# Adafruit_Feather_M0_WiFi.net
KiCad netlist of a schematic drawn in EAGLE
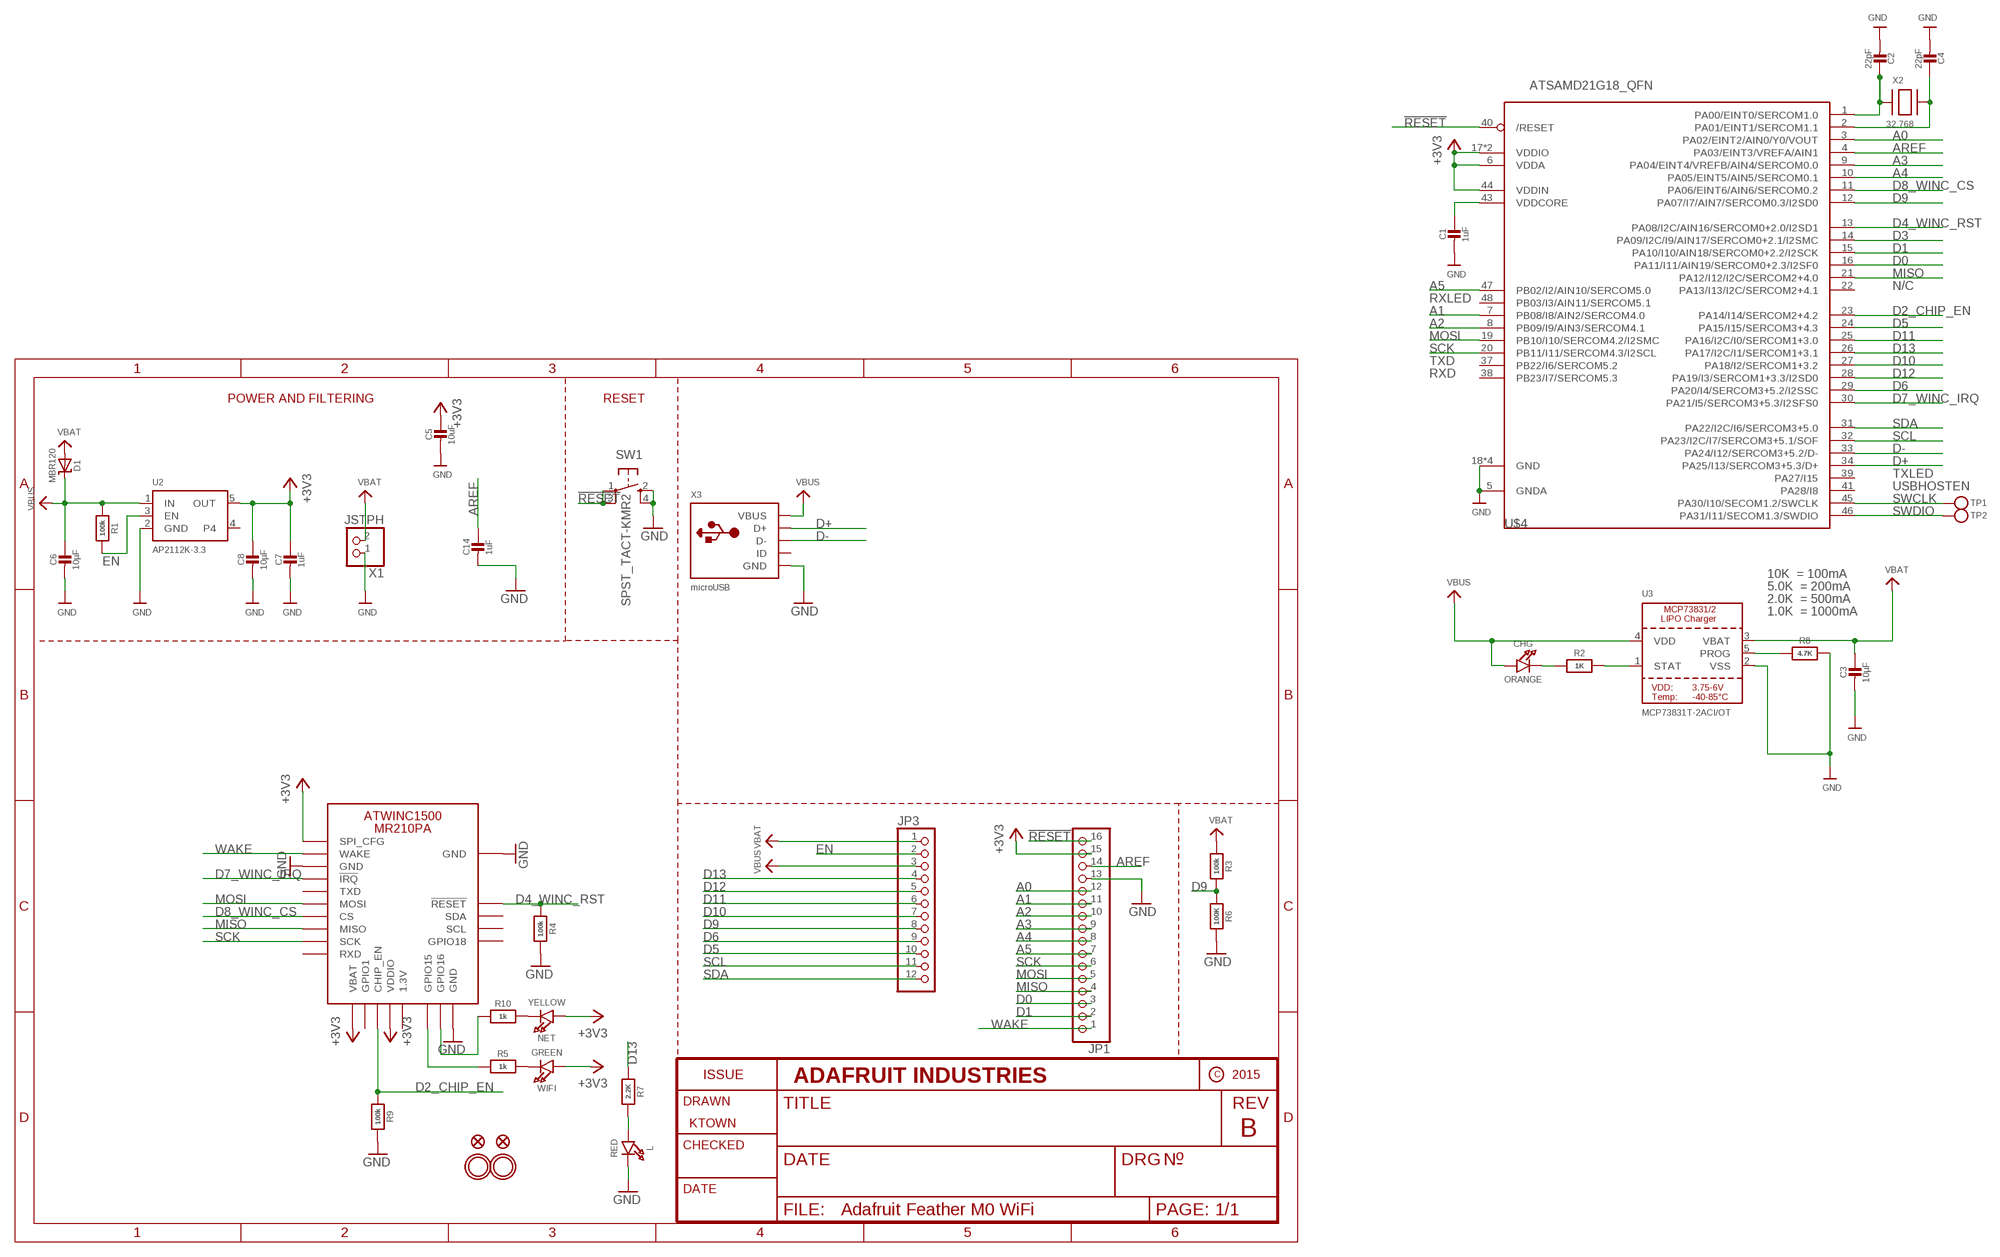
[diagram p0: schematic, sheet 1]

(export (version "E")
  (design (tool "Eeschema 10.0.6"))
  (components
    (comp (ref "C1")
      (value "1uF")
      (footprint "eagle-import:0603-NO")
      (libsource (lib "eagle-import") (part "CAP_CERAMIC0603_NO"))
    )
    (comp (ref "C2")
      (value "22pF")
      (footprint "eagle-import:0603-NO")
      (libsource (lib "eagle-import") (part "CAP_CERAMIC0603_NO"))
    )
    (comp (ref "C3")
      (value "10µF")
      (footprint "eagle-import:0805-NO")
      (libsource (lib "eagle-import") (part "CAP_CERAMIC0805-NOOUTLINE"))
    )
    (comp (ref "C4")
      (value "22pF")
      (footprint "eagle-import:0603-NO")
      (libsource (lib "eagle-import") (part "CAP_CERAMIC0603_NO"))
    )
    (comp (ref "C5")
      (value "10uF")
      (footprint "eagle-import:0805-NO")
      (libsource (lib "eagle-import") (part "CAP_CERAMIC0805-NOOUTLINE"))
    )
    (comp (ref "C6")
      (value "10µF")
      (footprint "eagle-import:0805-NO")
      (libsource (lib "eagle-import") (part "CAP_CERAMIC0805-NOOUTLINE"))
    )
    (comp (ref "C7")
      (value "1uF")
      (footprint "eagle-import:0603-NO")
      (libsource (lib "eagle-import") (part "CAP_CERAMIC0603_NO"))
    )
    (comp (ref "C8")
      (value "10µF")
      (footprint "eagle-import:0805-NO")
      (libsource (lib "eagle-import") (part "CAP_CERAMIC0805-NOOUTLINE"))
    )
    (comp (ref "C14")
      (value "1uF")
      (footprint "eagle-import:0603-NO")
      (libsource (lib "eagle-import") (part "CAP_CERAMIC0603_NO"))
    )
    (comp (ref "CHG")
      (value "ORANGE")
      (footprint "eagle-import:CHIPLED_0805_NOOUTLINE")
      (libsource (lib "eagle-import") (part "LED0805_NOOUTLINE"))
    )
    (comp (ref "D1")
      (value "MBR120")
      (footprint "eagle-import:SOD-123")
      (libsource (lib "eagle-import") (part "DIODE-SCHOTTKYSOD-123"))
    )
    (comp (ref "JP1")
      (value "HEADER-1X16ROUND")
      (footprint "eagle-import:1X16_ROUND")
      (libsource (lib "eagle-import") (part "HEADER-1X16ROUND"))
    )
    (comp (ref "JP3")
      (value "HEADER-1X12")
      (footprint "eagle-import:1X12_ROUND")
      (libsource (lib "eagle-import") (part "HEADER-1X12"))
    )
    (comp (ref "L")
      (value "RED")
      (footprint "eagle-import:CHIPLED_0805_NOOUTLINE")
      (libsource (lib "eagle-import") (part "LED0805_NOOUTLINE"))
    )
    (comp (ref "NET")
      (value "YELLOW")
      (footprint "eagle-import:CHIPLED_0805_NOOUTLINE")
      (libsource (lib "eagle-import") (part "LED0805_NOOUTLINE"))
    )
    (comp (ref "R1")
      (value "100k")
      (footprint "eagle-import:0603-NO")
      (libsource (lib "eagle-import") (part "RESISTOR_0603_NOOUT"))
    )
    (comp (ref "R2")
      (value "1K")
      (footprint "eagle-import:0603-NO")
      (libsource (lib "eagle-import") (part "RESISTOR_0603_NOOUT"))
    )
    (comp (ref "R3")
      (value "100k")
      (footprint "eagle-import:0603-NO")
      (libsource (lib "eagle-import") (part "RESISTOR_0603_NOOUT"))
    )
    (comp (ref "R4")
      (value "100k")
      (footprint "eagle-import:0603-NO")
      (libsource (lib "eagle-import") (part "RESISTOR_0603_NOOUT"))
    )
    (comp (ref "R5")
      (value "1k")
      (footprint "eagle-import:0603-NO")
      (libsource (lib "eagle-import") (part "RESISTOR_0603_NOOUT"))
    )
    (comp (ref "R6")
      (value "100K")
      (footprint "eagle-import:0603-NO")
      (libsource (lib "eagle-import") (part "RESISTOR_0603_NOOUT"))
    )
    (comp (ref "R7")
      (value "2.2K")
      (footprint "eagle-import:0603-NO")
      (libsource (lib "eagle-import") (part "RESISTOR_0603_NOOUT"))
    )
    (comp (ref "R8")
      (value "4.7K")
      (footprint "eagle-import:0603-NO")
      (libsource (lib "eagle-import") (part "RESISTOR_0603_NOOUT"))
    )
    (comp (ref "R9")
      (value "100k")
      (footprint "eagle-import:0603-NO")
      (libsource (lib "eagle-import") (part "RESISTOR_0603_NOOUT"))
    )
    (comp (ref "R10")
      (value "1k")
      (footprint "eagle-import:0603-NO")
      (libsource (lib "eagle-import") (part "RESISTOR_0603_NOOUT"))
    )
    (comp (ref "SW1")
      (value "SPST_TACT-KMR2")
      (footprint "eagle-import:KMR2")
      (libsource (lib "eagle-import") (part "SPST_TACT-KMR2"))
    )
    (comp (ref "TP1")
      (value "TESTPOINTROUND1.5MM")
      (footprint "eagle-import:TESTPOINT_ROUND_1.5MM")
      (libsource (lib "eagle-import") (part "TESTPOINTROUND1.5MM"))
    )
    (comp (ref "TP2")
      (value "TESTPOINTROUND1.5MM")
      (footprint "eagle-import:TESTPOINT_ROUND_1.5MM")
      (libsource (lib "eagle-import") (part "TESTPOINTROUND1.5MM"))
    )
    (comp (ref "U$4")
      (value "ATSAMD21G18_QFN")
      (footprint "eagle-import:TQFN48_7MM")
      (libsource (lib "eagle-import") (part "ATSAMD21J_QFN"))
    )
    (comp (ref "U$31")
      (value "MOUNTINGHOLE2.5")
      (footprint "eagle-import:MOUNTINGHOLE_2.5_PLATED")
      (libsource (lib "eagle-import") (part "MOUNTINGHOLE2.5"))
    )
    (comp (ref "U$32")
      (value "MOUNTINGHOLE2.5")
      (footprint "eagle-import:MOUNTINGHOLE_2.5_PLATED")
      (libsource (lib "eagle-import") (part "MOUNTINGHOLE2.5"))
    )
    (comp (ref "U$34")
      (value "FIDUCIAL\"\"")
      (footprint "eagle-import:FIDUCIAL_1MM")
      (libsource (lib "eagle-import") (part "FIDUCIAL{dblquote}{dblquote}"))
    )
    (comp (ref "U$35")
      (value "FIDUCIAL\"\"")
      (footprint "eagle-import:FIDUCIAL_1MM")
      (libsource (lib "eagle-import") (part "FIDUCIAL{dblquote}{dblquote}"))
    )
    (comp (ref "U2")
      (value "AP2112K-3.3")
      (footprint "eagle-import:SOT23-5")
      (libsource (lib "eagle-import") (part "VREG_SOT23-5"))
    )
    (comp (ref "U3")
      (value "MCP73831T-2ACI/OT")
      (footprint "eagle-import:SOT23-5")
      (libsource (lib "eagle-import") (part "MCP73831/2"))
    )
    (comp (ref "WIFI")
      (value "GREEN")
      (footprint "eagle-import:CHIPLED_0805_NOOUTLINE")
      (libsource (lib "eagle-import") (part "LED0805_NOOUTLINE"))
    )
    (comp (ref "X1")
      (value "JSTPH")
      (footprint "eagle-import:JSTPH2")
      (libsource (lib "eagle-import") (part "CON_JST_PH_2PIN"))
    )
    (comp (ref "X2")
      (value "32.768")
      (footprint "eagle-import:XTAL3215")
      (libsource (lib "eagle-import") (part "XTAL-3.2X1.5"))
    )
    (comp (ref "X3")
      (value "microUSB")
      (footprint "eagle-import:4UCONN_20329_V2")
      (libsource (lib "eagle-import") (part "USB_MICRO_20329_V2"))
    )
    (comp (ref "X4")
      (value "ATWINC1500_MR210PA")
      (footprint "eagle-import:ATWINC1500_MR210PA")
      (libsource (lib "eagle-import") (part "ATWINC1500_MR210PA"))
    )
  )
  (nets
    (net (code "1") (name "+3V3") (class "Default")
      (node (ref "C5") (pin "1") (pinfunction "1_1") (pintype "passive"))
      (node (ref "C7") (pin "1") (pinfunction "1_1") (pintype "passive"))
      (node (ref "C8") (pin "1") (pinfunction "1_1") (pintype "passive"))
      (node (ref "JP1") (pin "15") (pinfunction "15_15") (pintype "passive"))
      (node (ref "NET") (pin "A") (pinfunction "A_A") (pintype "passive"))
      (node (ref "U$4") (pin "17") (pinfunction "VDDIO_17") (pintype "power_in"))
      (node (ref "U$4") (pin "36") (pinfunction "VDDIO_36") (pintype "power_in"))
      (node (ref "U$4") (pin "44") (pinfunction "VDDIN_44") (pintype "power_in"))
      (node (ref "U$4") (pin "6") (pinfunction "VDDA_6") (pintype "power_in"))
      (node (ref "U2") (pin "5") (pinfunction "OUT_5") (pintype "power_in"))
      (node (ref "WIFI") (pin "A") (pinfunction "A_A") (pintype "passive"))
      (node (ref "X4") (pin "J10") (pinfunction "SPI_CFG_J10") (pintype "input"))
      (node (ref "X4") (pin "J20") (pinfunction "VBAT_J20") (pintype "power_in"))
      (node (ref "X4") (pin "J23") (pinfunction "VDDIO_J23") (pintype "power_in"))
    )
    (net (code "2") (name "/A0") (class "Default")
      (node (ref "JP1") (pin "12") (pinfunction "12_12") (pintype "passive"))
      (node (ref "U$4") (pin "3") (pinfunction "PA02/EINT2/AIN0/Y0/VOUT_3") (pintype "bidirectional"))
    )
    (net (code "3") (name "/A1") (class "Default")
      (node (ref "JP1") (pin "11") (pinfunction "11_11") (pintype "passive"))
      (node (ref "U$4") (pin "7") (pinfunction "PB08/I8/AIN2/SERCOM4.0_7") (pintype "bidirectional"))
    )
    (net (code "4") (name "/A2") (class "Default")
      (node (ref "JP1") (pin "10") (pinfunction "10_10") (pintype "passive"))
      (node (ref "U$4") (pin "8") (pinfunction "PB09/I9/AIN3/SERCOM4.1_8") (pintype "bidirectional"))
    )
    (net (code "5") (name "/A3") (class "Default")
      (node (ref "JP1") (pin "9") (pinfunction "9_9") (pintype "passive"))
      (node (ref "U$4") (pin "9") (pinfunction "PA04/EINT4/VREFB/AIN4/SERCOM0.0_9") (pintype "bidirectional"))
    )
    (net (code "6") (name "/A4") (class "Default")
      (node (ref "JP1") (pin "8") (pinfunction "8_8") (pintype "passive"))
      (node (ref "U$4") (pin "10") (pinfunction "PA05/EINT5/AIN5/SERCOM0.1_10") (pintype "bidirectional"))
    )
    (net (code "7") (name "/A5") (class "Default")
      (node (ref "JP1") (pin "7") (pinfunction "7_7") (pintype "passive"))
      (node (ref "U$4") (pin "47") (pinfunction "PB02/I2/AIN10/SERCOM5.0_47") (pintype "bidirectional"))
    )
    (net (code "8") (name "/AREF") (class "Default")
      (node (ref "C14") (pin "1") (pinfunction "1_1") (pintype "passive"))
      (node (ref "JP1") (pin "14") (pinfunction "14_14") (pintype "passive"))
      (node (ref "U$4") (pin "4") (pinfunction "PA03/EINT3/VREFA/AIN1_4") (pintype "bidirectional"))
    )
    (net (code "9") (name "/D+") (class "Default")
      (node (ref "U$4") (pin "34") (pinfunction "PA25/I13/SERCOM3+5.3/D+_34") (pintype "bidirectional"))
      (node (ref "X3") (pin "D+") (pinfunction "D+_D+") (pintype "bidirectional"))
    )
    (net (code "10") (name "/D-") (class "Default")
      (node (ref "U$4") (pin "33") (pinfunction "PA24/I12/SERCOM3+5.2/D-_33") (pintype "bidirectional"))
      (node (ref "X3") (pin "D-") (pinfunction "D-_D-") (pintype "bidirectional"))
    )
    (net (code "11") (name "/D0") (class "Default")
      (node (ref "JP1") (pin "3") (pinfunction "3_3") (pintype "passive"))
      (node (ref "U$4") (pin "16") (pinfunction "PA11/I11/AIN19/SERCOM0+2.3/I2SF0_16") (pintype "bidirectional"))
    )
    (net (code "12") (name "/D1") (class "Default")
      (node (ref "JP1") (pin "2") (pinfunction "2_2") (pintype "passive"))
      (node (ref "U$4") (pin "15") (pinfunction "PA10/I10/AIN18/SERCOM0+2.2/I2SCK_15") (pintype "bidirectional"))
    )
    (net (code "13") (name "/D2_CHIP_EN") (class "Default")
      (node (ref "R9") (pin "1") (pinfunction "1_1") (pintype "passive"))
      (node (ref "U$4") (pin "23") (pinfunction "PA14/I14/SERCOM2+4.2_23") (pintype "bidirectional"))
      (node (ref "X4") (pin "J22") (pinfunction "CHIP_EN_J22") (pintype "input"))
    )
    (net (code "14") (name "/D3") (class "Default")
      (node (ref "U$4") (pin "14") (pinfunction "PA09/I2C/I9/AIN17/SERCOM0+2.1/I2SMC_14") (pintype "bidirectional"))
    )
    (net (code "15") (name "/D4_WINC_RST") (class "Default")
      (node (ref "R4") (pin "1") (pinfunction "1_1") (pintype "passive"))
      (node (ref "U$4") (pin "13") (pinfunction "PA08/I2C/AIN16/SERCOM0+2.0/I2SD1_13") (pintype "bidirectional"))
      (node (ref "X4") (pin "J4") (pinfunction "~{RESET}_J4") (pintype "input"))
    )
    (net (code "16") (name "/D5") (class "Default")
      (node (ref "JP3") (pin "10") (pinfunction "10_10") (pintype "passive"))
      (node (ref "U$4") (pin "24") (pinfunction "PA15/I15/SERCOM3+4.3_24") (pintype "bidirectional"))
    )
    (net (code "17") (name "/D6") (class "Default")
      (node (ref "JP3") (pin "9") (pinfunction "9_9") (pintype "passive"))
      (node (ref "U$4") (pin "29") (pinfunction "PA20/I4/SERCOM3+5.2/I2SSC_29") (pintype "bidirectional"))
    )
    (net (code "18") (name "/D7_WINC_IRQ") (class "Default")
      (node (ref "U$4") (pin "30") (pinfunction "PA21/I5/SERCOM3+5.3/I2SFS0_30") (pintype "bidirectional"))
      (node (ref "X4") (pin "J13") (pinfunction "~{IRQ}_J13") (pintype "output"))
    )
    (net (code "19") (name "/D8_WINC_CS") (class "Default")
      (node (ref "U$4") (pin "11") (pinfunction "PA06/EINT6/AIN6/SERCOM0.2_11") (pintype "bidirectional"))
      (node (ref "X4") (pin "J16") (pinfunction "CS_J16") (pintype "input"))
    )
    (net (code "20") (name "/D9") (class "Default")
      (node (ref "JP3") (pin "8") (pinfunction "8_8") (pintype "passive"))
      (node (ref "R3") (pin "2") (pinfunction "2_2") (pintype "passive"))
      (node (ref "R6") (pin "1") (pinfunction "1_1") (pintype "passive"))
      (node (ref "U$4") (pin "12") (pinfunction "PA07/I7/AIN7/SERCOM0.3/I2SD0_12") (pintype "bidirectional"))
    )
    (net (code "21") (name "/D10") (class "Default")
      (node (ref "JP3") (pin "7") (pinfunction "7_7") (pintype "passive"))
      (node (ref "U$4") (pin "27") (pinfunction "PA18/I2/SERCOM1+3.2_27") (pintype "bidirectional"))
    )
    (net (code "22") (name "/D11") (class "Default")
      (node (ref "JP3") (pin "6") (pinfunction "6_6") (pintype "passive"))
      (node (ref "U$4") (pin "25") (pinfunction "PA16/I2C/I0/SERCOM1+3.0_25") (pintype "bidirectional"))
    )
    (net (code "23") (name "/D12") (class "Default")
      (node (ref "JP3") (pin "5") (pinfunction "5_5") (pintype "passive"))
      (node (ref "U$4") (pin "28") (pinfunction "PA19/I3/SERCOM1+3.3/I2SD0_28") (pintype "bidirectional"))
    )
    (net (code "24") (name "/D13") (class "Default")
      (node (ref "JP3") (pin "4") (pinfunction "4_4") (pintype "passive"))
      (node (ref "R7") (pin "1") (pinfunction "1_1") (pintype "passive"))
      (node (ref "U$4") (pin "26") (pinfunction "PA17/I2C/I1/SERCOM1+3.1_26") (pintype "bidirectional"))
    )
    (net (code "25") (name "/EN") (class "Default")
      (node (ref "JP3") (pin "2") (pinfunction "2_2") (pintype "passive"))
      (node (ref "R1") (pin "2") (pinfunction "2_2") (pintype "passive"))
      (node (ref "U2") (pin "3") (pinfunction "EN_3") (pintype "input"))
    )
    (net (code "26") (name "/MISO") (class "Default")
      (node (ref "JP1") (pin "4") (pinfunction "4_4") (pintype "passive"))
      (node (ref "U$4") (pin "21") (pinfunction "PA12/I12/I2C/SERCOM2+4.0_21") (pintype "bidirectional"))
      (node (ref "X4") (pin "J17") (pinfunction "MISO_J17") (pintype "output"))
    )
    (net (code "27") (name "/MOSI") (class "Default")
      (node (ref "JP1") (pin "5") (pinfunction "5_5") (pintype "passive"))
      (node (ref "U$4") (pin "19") (pinfunction "PB10/I10/SERCOM4.2/I2SMC_19") (pintype "bidirectional"))
      (node (ref "X4") (pin "J15") (pinfunction "MOSI_J15") (pintype "input"))
    )
    (net (code "28") (name "/SCK") (class "Default")
      (node (ref "JP1") (pin "6") (pinfunction "6_6") (pintype "passive"))
      (node (ref "U$4") (pin "20") (pinfunction "PB11/I11/SERCOM4.3/I2SCL_20") (pintype "bidirectional"))
      (node (ref "X4") (pin "J18") (pinfunction "SCK_J18") (pintype "input"))
    )
    (net (code "29") (name "/SCL") (class "Default")
      (node (ref "JP3") (pin "11") (pinfunction "11_11") (pintype "passive"))
      (node (ref "U$4") (pin "32") (pinfunction "PA23/I2C/I7/SERCOM3+5.1/SOF_32") (pintype "bidirectional"))
    )
    (net (code "30") (name "/SDA") (class "Default")
      (node (ref "JP3") (pin "12") (pinfunction "12_12") (pintype "passive"))
      (node (ref "U$4") (pin "31") (pinfunction "PA22/I2C/I6/SERCOM3+5.0_31") (pintype "bidirectional"))
    )
    (net (code "31") (name "/SWCLK") (class "Default")
      (node (ref "TP1") (pin "P$1") (pinfunction "P$1_P$1") (pintype "bidirectional"))
      (node (ref "U$4") (pin "45") (pinfunction "PA30/I10/SECOM1.2/SWCLK_45") (pintype "bidirectional"))
    )
    (net (code "32") (name "/SWDIO") (class "Default")
      (node (ref "TP2") (pin "P$1") (pinfunction "P$1_P$1") (pintype "bidirectional"))
      (node (ref "U$4") (pin "46") (pinfunction "PA31/I11/SECOM1.3/SWDIO_46") (pintype "bidirectional"))
    )
    (net (code "33") (name "/WAKE") (class "Default")
      (node (ref "JP1") (pin "1") (pinfunction "1_1") (pintype "passive"))
      (node (ref "X4") (pin "J11") (pinfunction "WAKE_J11") (pintype "input"))
    )
    (net (code "34") (name "/~{RESET}") (class "Default")
      (node (ref "JP1") (pin "16") (pinfunction "16_16") (pintype "passive"))
      (node (ref "SW1") (pin "1") (pinfunction "P_1") (pintype "passive"))
      (node (ref "SW1") (pin "3") (pinfunction "P1_3") (pintype "passive"))
      (node (ref "U$4") (pin "40") (pinfunction "/RESET_40") (pintype "bidirectional"))
    )
    (net (code "35") (name "GND") (class "Default")
      (node (ref "C1") (pin "2") (pinfunction "2_2") (pintype "passive"))
      (node (ref "C14") (pin "2") (pinfunction "2_2") (pintype "passive"))
      (node (ref "C2") (pin "2") (pinfunction "2_2") (pintype "passive"))
      (node (ref "C3") (pin "2") (pinfunction "2_2") (pintype "passive"))
      (node (ref "C4") (pin "2") (pinfunction "2_2") (pintype "passive"))
      (node (ref "C5") (pin "2") (pinfunction "2_2") (pintype "passive"))
      (node (ref "C6") (pin "2") (pinfunction "2_2") (pintype "passive"))
      (node (ref "C7") (pin "2") (pinfunction "2_2") (pintype "passive"))
      (node (ref "C8") (pin "2") (pinfunction "2_2") (pintype "passive"))
      (node (ref "JP1") (pin "13") (pinfunction "13_13") (pintype "passive"))
      (node (ref "L") (pin "C") (pinfunction "C_C") (pintype "passive"))
      (node (ref "R4") (pin "2") (pinfunction "2_2") (pintype "passive"))
      (node (ref "R6") (pin "2") (pinfunction "2_2") (pintype "passive"))
      (node (ref "R8") (pin "2") (pinfunction "2_2") (pintype "passive"))
      (node (ref "R9") (pin "2") (pinfunction "2_2") (pintype "passive"))
      (node (ref "SW1") (pin "2") (pinfunction "S_2") (pintype "passive"))
      (node (ref "SW1") (pin "4") (pinfunction "S1_4") (pintype "passive"))
      (node (ref "U$4") (pin "18") (pinfunction "GND_18") (pintype "power_in"))
      (node (ref "U$4") (pin "35") (pinfunction "GND_35") (pintype "power_in"))
      (node (ref "U$4") (pin "42") (pinfunction "GND_42") (pintype "power_in"))
      (node (ref "U$4") (pin "5") (pinfunction "GNDA_5") (pintype "power_in"))
      (node (ref "U$4") (pin "THERMAL") (pinfunction "GND_THERMAL") (pintype "power_in"))
      (node (ref "U2") (pin "2") (pinfunction "GND_2") (pintype "power_in"))
      (node (ref "U3") (pin "2") (pinfunction "VSS_2") (pintype "power_in"))
      (node (ref "X1") (pin "1") (pinfunction "1_1") (pintype "passive"))
      (node (ref "X3") (pin "BASE@1") (pinfunction "GND_BASE@1") (pintype "power_in"))
      (node (ref "X3") (pin "BASE@2") (pinfunction "GND_BASE@2") (pintype "power_in"))
      (node (ref "X3") (pin "GND") (pinfunction "GND_GND") (pintype "power_in"))
      (node (ref "X3") (pin "SPRT@1") (pinfunction "GND_SPRT@1") (pintype "power_in"))
      (node (ref "X3") (pin "SPRT@2") (pinfunction "GND_SPRT@2") (pintype "power_in"))
      (node (ref "X3") (pin "SPRT@3") (pinfunction "GND_SPRT@3") (pintype "power_in"))
      (node (ref "X3") (pin "SPRT@4") (pinfunction "GND_SPRT@4") (pintype "power_in"))
      (node (ref "X4") (pin "J12") (pinfunction "GND_J12") (pintype "power_in"))
      (node (ref "X4") (pin "J28") (pinfunction "GND_J28") (pintype "power_in"))
      (node (ref "X4") (pin "J9") (pinfunction "GND_J9") (pintype "bidirectional"))
    )
    (net (code "36") (name "Net-(CHG-PadC)") (class "Default")
      (node (ref "CHG") (pin "C") (pinfunction "C_C") (pintype "passive"))
      (node (ref "R2") (pin "1") (pinfunction "1_1") (pintype "passive"))
    )
    (net (code "37") (name "Net-(L-PadA)") (class "Default")
      (node (ref "L") (pin "A") (pinfunction "A_A") (pintype "passive"))
      (node (ref "R7") (pin "2") (pinfunction "2_2") (pintype "passive"))
    )
    (net (code "38") (name "Net-(NET-PadC)") (class "Default")
      (node (ref "NET") (pin "C") (pinfunction "C_C") (pintype "passive"))
      (node (ref "R10") (pin "2") (pinfunction "2_2") (pintype "passive"))
    )
    (net (code "39") (name "Net-(R5-Pad2)") (class "Default")
      (node (ref "R5") (pin "2") (pinfunction "2_2") (pintype "passive"))
      (node (ref "WIFI") (pin "C") (pinfunction "C_C") (pintype "passive"))
    )
    (net (code "40") (name "Net-(U$4-PA00{slash}EINT0{slash}SERCOM1.0)") (class "Default")
      (node (ref "C2") (pin "1") (pinfunction "1_1") (pintype "passive"))
      (node (ref "U$4") (pin "1") (pinfunction "PA00/EINT0/SERCOM1.0_1") (pintype "bidirectional"))
      (node (ref "X2") (pin "P$1") (pinfunction "P$1_P$1") (pintype "bidirectional"))
    )
    (net (code "41") (name "Net-(U$4-PA01{slash}EINT1{slash}SERCOM1.1)") (class "Default")
      (node (ref "C4") (pin "1") (pinfunction "1_1") (pintype "passive"))
      (node (ref "U$4") (pin "2") (pinfunction "PA01/EINT1/SERCOM1.1_2") (pintype "bidirectional"))
      (node (ref "X2") (pin "P$2") (pinfunction "P$2_P$2") (pintype "bidirectional"))
    )
    (net (code "42") (name "Net-(U$4-VDDCORE)") (class "Default")
      (node (ref "C1") (pin "1") (pinfunction "1_1") (pintype "passive"))
      (node (ref "U$4") (pin "43") (pinfunction "VDDCORE_43") (pintype "power_in"))
    )
    (net (code "43") (name "Net-(U3-PROG)") (class "Default")
      (node (ref "R8") (pin "1") (pinfunction "1_1") (pintype "passive"))
      (node (ref "U3") (pin "5") (pinfunction "PROG_5") (pintype "input"))
    )
    (net (code "44") (name "Net-(U3-STAT)") (class "Default")
      (node (ref "R2") (pin "2") (pinfunction "2_2") (pintype "passive"))
      (node (ref "U3") (pin "1") (pinfunction "STAT_1") (pintype "output"))
    )
    (net (code "45") (name "Net-(X4-GPIO15)") (class "Default")
      (node (ref "R5") (pin "1") (pinfunction "1_1") (pintype "passive"))
      (node (ref "X4") (pin "J26") (pinfunction "GPIO15_J26") (pintype "bidirectional"))
    )
    (net (code "46") (name "Net-(X4-GPIO16)") (class "Default")
      (node (ref "R10") (pin "1") (pinfunction "1_1") (pintype "passive"))
      (node (ref "X4") (pin "J27") (pinfunction "GPIO16_J27") (pintype "bidirectional"))
    )
    (net (code "47") (name "VBAT") (class "Default")
      (node (ref "C3") (pin "1") (pinfunction "1_1") (pintype "passive"))
      (node (ref "D1") (pin "A") (pinfunction "A_A") (pintype "passive"))
      (node (ref "JP3") (pin "1") (pinfunction "1_1") (pintype "passive"))
      (node (ref "R3") (pin "1") (pinfunction "1_1") (pintype "passive"))
      (node (ref "U3") (pin "3") (pinfunction "VBAT_3") (pintype "power_in"))
      (node (ref "X1") (pin "2") (pinfunction "2_2") (pintype "passive"))
    )
    (net (code "48") (name "VBUS") (class "Default")
      (node (ref "C6") (pin "1") (pinfunction "1_1") (pintype "passive"))
      (node (ref "CHG") (pin "A") (pinfunction "A_A") (pintype "passive"))
      (node (ref "D1") (pin "C") (pinfunction "C_C") (pintype "passive"))
      (node (ref "JP3") (pin "3") (pinfunction "3_3") (pintype "passive"))
      (node (ref "R1") (pin "1") (pinfunction "1_1") (pintype "passive"))
      (node (ref "U2") (pin "1") (pinfunction "IN_1") (pintype "power_in"))
      (node (ref "U3") (pin "4") (pinfunction "VDD_4") (pintype "power_in"))
      (node (ref "X3") (pin "VBUS") (pinfunction "VBUS_VBUS") (pintype "power_in"))
    )
    (net (code "49") (name "unconnected-(U$4-PA13{slash}I13{slash}I2C{slash}SERCOM2+4.1-Pad22)") (class "Default")
      (node (ref "U$4") (pin "22") (pinfunction "PA13/I13/I2C/SERCOM2+4.1_22") (pintype "bidirectional"))
    )
    (net (code "50") (name "unconnected-(U$4-PA27{slash}I15-Pad39)") (class "Default")
      (node (ref "U$4") (pin "39") (pinfunction "PA27/I15_39") (pintype "bidirectional"))
    )
    (net (code "51") (name "unconnected-(U$4-PA28{slash}I8-Pad41)") (class "Default")
      (node (ref "U$4") (pin "41") (pinfunction "PA28/I8_41") (pintype "bidirectional"))
    )
    (net (code "52") (name "unconnected-(U$4-PB03{slash}I3{slash}AIN11{slash}SERCOM5.1-Pad48)") (class "Default")
      (node (ref "U$4") (pin "48") (pinfunction "PB03/I3/AIN11/SERCOM5.1_48") (pintype "bidirectional"))
    )
    (net (code "53") (name "unconnected-(U$4-PB22{slash}I6{slash}SERCOM5.2-Pad37)") (class "Default")
      (node (ref "U$4") (pin "37") (pinfunction "PB22/I6/SERCOM5.2_37") (pintype "bidirectional"))
    )
    (net (code "54") (name "unconnected-(U$4-PB23{slash}I7{slash}SERCOM5.3-Pad38)") (class "Default")
      (node (ref "U$4") (pin "38") (pinfunction "PB23/I7/SERCOM5.3_38") (pintype "bidirectional"))
    )
    (net (code "55") (name "unconnected-(U2-P4-Pad4)") (class "Default")
      (node (ref "U2") (pin "4") (pinfunction "P4_4") (pintype "bidirectional"))
    )
    (net (code "56") (name "unconnected-(X3-PadID)") (class "Default")
      (node (ref "X3") (pin "ID") (pinfunction "ID_ID") (pintype "bidirectional"))
    )
    (net (code "57") (name "unconnected-(X4-1.3V-PadJ24)") (class "Default")
      (node (ref "X4") (pin "J24") (pinfunction "1.3V_J24") (pintype "passive"))
    )
    (net (code "58") (name "unconnected-(X4-GPIO1-PadJ21)") (class "Default")
      (node (ref "X4") (pin "J21") (pinfunction "GPIO1_J21") (pintype "bidirectional"))
    )
    (net (code "59") (name "unconnected-(X4-GPIO18-PadJ1)") (class "Default")
      (node (ref "X4") (pin "J1") (pinfunction "GPIO18_J1") (pintype "bidirectional"))
    )
    (net (code "60") (name "unconnected-(X4-RXD-PadJ19)") (class "Default")
      (node (ref "X4") (pin "J19") (pinfunction "RXD_J19") (pintype "input"))
    )
    (net (code "61") (name "unconnected-(X4-SCL-PadJ2)") (class "Default")
      (node (ref "X4") (pin "J2") (pinfunction "SCL_J2") (pintype "bidirectional"))
    )
    (net (code "62") (name "unconnected-(X4-SDA-PadJ3)") (class "Default")
      (node (ref "X4") (pin "J3") (pinfunction "SDA_J3") (pintype "bidirectional"))
    )
    (net (code "63") (name "unconnected-(X4-TXD-PadJ14)") (class "Default")
      (node (ref "X4") (pin "J14") (pinfunction "TXD_J14") (pintype "output"))
    )
  )
)
